# ai.net
KiCad netlist of a schematic drawn in Altium Designer
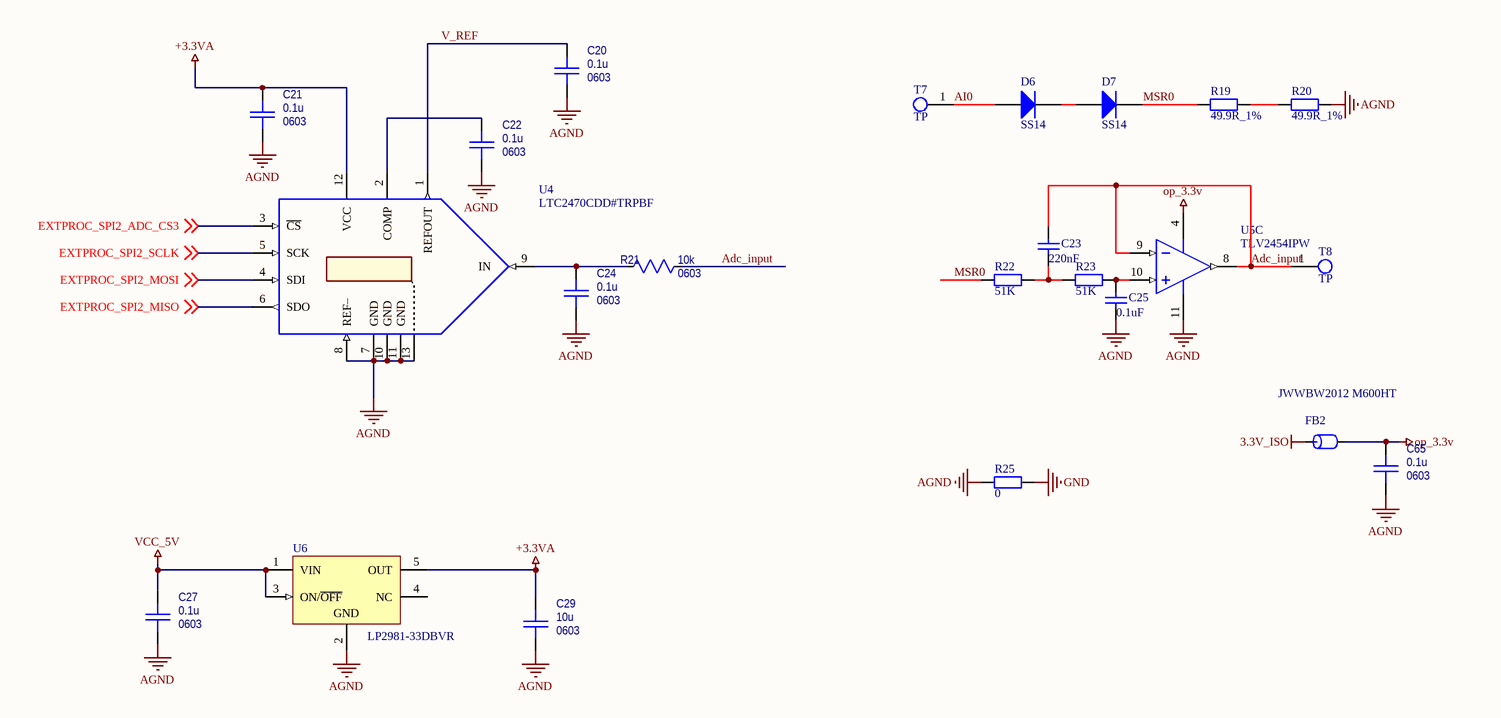
[diagram p0: ai.SchDoc]

(export (version "E")
  (design (tool "Eeschema 10.0.6"))
  (components
    (comp (ref "C20")
      (value "0.1u")
      (footprint "CAPC1608X092N_0603")
      (description "Capacitor, MLCC")
      (fields
        (field (name "PARTNUMBER") "C0603C104M5RACTU")
        (field (name "TOLERANCE") "[tol]")
        (field (name "PACKAGE") "0603")
      )
      (libsource (lib "Karl") (part "Capacitor_0603"))
    )
    (comp (ref "C21")
      (value "0.1u")
      (footprint "CAPC1608X092N_0603")
      (description "Capacitor, MLCC")
      (fields
        (field (name "PARTNUMBER") "C0603C104M5RACTU")
        (field (name "TOLERANCE") "[tol]")
        (field (name "PACKAGE") "0603")
      )
      (libsource (lib "Karl") (part "Capacitor_0603"))
    )
    (comp (ref "C22")
      (value "0.1u")
      (footprint "CAPC1608X092N_0603")
      (description "Capacitor, MLCC")
      (fields
        (field (name "PARTNUMBER") "C0603C104M5RACTU")
        (field (name "TOLERANCE") "[tol]")
        (field (name "PACKAGE") "0603")
      )
      (libsource (lib "Karl") (part "Capacitor_0603"))
    )
    (comp (ref "C23")
      (value "220nF")
      (footprint "0805C")
      (description "Capacitor")
      (fields (field (name "PUBLISHER") "Altium Limited"))
      (libsource (lib "Miscellaneous Devices") (part "Cap"))
    )
    (comp (ref "C24")
      (value "0.1u")
      (footprint "CAPC1608X092N_0603")
      (description "Capacitor, MLCC")
      (fields
        (field (name "PARTNUMBER") "C0603C104M5RACTU")
        (field (name "TOLERANCE") "[tol]")
        (field (name "PACKAGE") "0603")
      )
      (libsource (lib "Karl") (part "Capacitor_0603"))
    )
    (comp (ref "C25")
      (value "0.1uF")
      (footprint "0603C")
      (description "Capacitor")
      (fields (field (name "PUBLISHER") "Altium Limited"))
      (libsource (lib "Miscellaneous Devices") (part "Cap"))
    )
    (comp (ref "C27")
      (value "0.1u")
      (footprint "CAPC1608X092N_0603")
      (description "Capacitor, MLCC")
      (fields
        (field (name "PARTNUMBER") "C0603C104M5RACTU")
        (field (name "TOLERANCE") "[tol]")
        (field (name "PACKAGE") "0603")
      )
      (libsource (lib "Karl") (part "Capacitor_0603"))
    )
    (comp (ref "C29")
      (value "10u")
      (footprint "CAPC1608X092N_0603")
      (description "Capacitor, MLCC")
      (fields
        (field (name "PARTNUMBER") "GRM188R61A106KE69D")
        (field (name "TOLERANCE") "[tol]")
        (field (name "PACKAGE") "0603")
      )
      (libsource (lib "Karl") (part "Capacitor_0603"))
    )
    (comp (ref "C65")
      (value "0.1u")
      (footprint "CAPC1608X092N_0603")
      (description "Capacitor, MLCC")
      (fields
        (field (name "PARTNUMBER") "C0603C104M5RACTU")
        (field (name "TOLERANCE") "[tol]")
        (field (name "PACKAGE") "0603")
      )
      (libsource (lib "Karl") (part "Capacitor_0603"))
    )
    (comp (ref "D6")
      (value "SS14")
      (footprint "DO-214AC")
      (description "Default Diode")
      (fields (field (name "PUBLISHER") "Altium Limited"))
      (libsource (lib "Miscellaneous Devices") (part "Diode"))
    )
    (comp (ref "D7")
      (value "SS14")
      (footprint "DO-214AC")
      (description "Default Diode")
      (fields (field (name "PUBLISHER") "Altium Limited"))
      (libsource (lib "Miscellaneous Devices") (part "Diode"))
    )
    (comp (ref "FB2")
      (value "JWWBW2012 M600HT")
      (footprint "0805R")
      (libsource (lib "Schlib_20110825") (part "FB"))
    )
    (comp (ref "R19") (value "49.9R_1%") (footprint "0805R") (libsource (lib "MQlibrary") (part "Res0805M")))
    (comp (ref "R20") (value "49.9R_1%") (footprint "0805R") (libsource (lib "MQlibrary") (part "Res0805M")))
    (comp (ref "R21")
      (value "10k")
      (footprint "RESC1608X055N_0603")
      (description "Resistor, Standard")
      (fields
        (field (name "PARTNUMBER") "RR0816P-103-D")
        (field (name "TOLERANCE") "tol")
        (field (name "PACKAGE") "0603")
      )
      (libsource (lib "Karl") (part "Resistor_0603"))
    )
    (comp (ref "R22") (value "51K") (footprint "0603R") (libsource (lib "MQlibrary") (part "Res0805M")))
    (comp (ref "R23") (value "51K") (footprint "0603R") (libsource (lib "MQlibrary") (part "Res0805M")))
    (comp (ref "R25") (value "0") (footprint "1206R") (libsource (lib "MQlibrary") (part "Res0805M")))
    (comp (ref "T7") (value "TP") (footprint "TPD") (libsource (lib "Schlib_20110825") (part "TP")))
    (comp (ref "T8") (value "TP") (footprint "TPD") (libsource (lib "Schlib_20110825") (part "TP")))
    (comp (ref "U4")
      (value "LTC2470CDD#TRPBF")
      (footprint "LT-DD-12_V")
      (description "16-bit Analog-to-digital Converters, 12-pin SON (DD-12), 0 to 70 degC, Pb-Free, Tape and Reel")
      (libsource (lib "Bogen") (part "LTC2470CDD#TRPBF"))
    )
    (comp (ref "U5")
      (value "TLV2454IPW")
      (footprint "TSSOP14")
      (description "Quad High-speed, Ultra Low-power, Single-Supply TTL comparator")
      (fields (field (name "PUBLISHER") "Altium Limited"))
      (libsource (lib "Maxim Analog Comparator") (part "MAX908EPD"))
    )
    (comp (ref "U6")
      (value "LP2981-33DBVR")
      (footprint "DBV0005A_M")
      (description "Micropower 100 mA Ultra Low-Dropout Regulator, 5-pin SOT-23, Pb-Free")
      (libsource (lib "Bogen") (part "LP2981-33DBVR"))
    )
  )
  (nets
    (net (code "1") (name "+3.3VA") (class "Default")
      (node (ref "C21") (pin "1") (pinfunction "1_1") (pintype "passive"))
      (node (ref "C29") (pin "1") (pinfunction "1_1") (pintype "passive"))
      (node (ref "U4") (pin "12") (pinfunction "VCC_12") (pintype "power_in"))
      (node (ref "U6") (pin "5") (pinfunction "OUT_5") (pintype "power_in"))
    )
    (net (code "2") (name "/AI0") (class "Default")
      (node (ref "D6") (pin "1") (pinfunction "A_1") (pintype "passive"))
      (node (ref "T7") (pin "1") (pintype "passive"))
    )
    (net (code "3") (name "/Adc_input") (class "Default")
      (node (ref "C23") (pin "2") (pinfunction "2_2") (pintype "passive"))
      (node (ref "R21") (pin "1") (pinfunction "1_1") (pintype "passive"))
      (node (ref "T8") (pin "1") (pintype "passive"))
      (node (ref "U5") (pin "8") (pinfunction "OUT_8") (pintype "output"))
      (node (ref "U5") (pin "9") (pinfunction "IN-_9") (pintype "input"))
    )
    (net (code "4") (name "/MSR0") (class "Default")
      (node (ref "D7") (pin "2") (pinfunction "K_2") (pintype "passive"))
      (node (ref "R19") (pin "2") (pinfunction "2_2") (pintype "passive"))
      (node (ref "R22") (pin "2") (pinfunction "2_2") (pintype "passive"))
    )
    (net (code "5") (name "/V_REF") (class "Default")
      (node (ref "C20") (pin "1") (pinfunction "1_1") (pintype "passive"))
      (node (ref "U4") (pin "1") (pinfunction "REFOUT_1") (pintype "output"))
    )
    (net (code "6") (name "3.3V_ISO") (class "Default") (node (ref "FB2") (pin "1") (pintype "passive")))
    (net (code "7") (name "AGND") (class "Default")
      (node (ref "C20") (pin "2") (pinfunction "2_2") (pintype "passive"))
      (node (ref "C21") (pin "2") (pinfunction "2_2") (pintype "passive"))
      (node (ref "C22") (pin "2") (pinfunction "2_2") (pintype "passive"))
      (node (ref "C24") (pin "2") (pinfunction "2_2") (pintype "passive"))
      (node (ref "C25") (pin "1") (pinfunction "1_1") (pintype "passive"))
      (node (ref "C27") (pin "2") (pinfunction "2_2") (pintype "passive"))
      (node (ref "C29") (pin "2") (pinfunction "2_2") (pintype "passive"))
      (node (ref "C65") (pin "2") (pinfunction "2_2") (pintype "passive"))
      (node (ref "R20") (pin "1") (pinfunction "1_1") (pintype "passive"))
      (node (ref "R25") (pin "2") (pinfunction "2_2") (pintype "passive"))
      (node (ref "U4") (pin "10") (pinfunction "GND_10") (pintype "power_in"))
      (node (ref "U4") (pin "11") (pinfunction "GND_11") (pintype "power_in"))
      (node (ref "U4") (pin "13") (pinfunction "EP_13") (pintype "power_in"))
      (node (ref "U4") (pin "7") (pinfunction "GND_7") (pintype "power_in"))
      (node (ref "U4") (pin "8") (pinfunction "REF–_8") (pintype "input"))
      (node (ref "U5") (pin "11") (pinfunction "GND_11") (pintype "power_in"))
      (node (ref "U6") (pin "2") (pinfunction "GND_2") (pintype "power_in"))
    )
    (net (code "8") (name "EXTPROC_SPI2_ADC_CS3") (class "Default")
      (node (ref "U4") (pin "3") (pinfunction "~{CS}_3") (pintype "input"))
    )
    (net (code "9") (name "EXTPROC_SPI2_MISO") (class "Default")
      (node (ref "U4") (pin "6") (pinfunction "SDO_6") (pintype "output"))
    )
    (net (code "10") (name "EXTPROC_SPI2_MOSI") (class "Default")
      (node (ref "U4") (pin "4") (pinfunction "SDI_4") (pintype "input"))
    )
    (net (code "11") (name "EXTPROC_SPI2_SCLK") (class "Default")
      (node (ref "U4") (pin "5") (pinfunction "SCK_5") (pintype "input"))
    )
    (net (code "12") (name "GND") (class "Default")
      (node (ref "R25") (pin "1") (pinfunction "1_1") (pintype "passive"))
    )
    (net (code "13") (name "Net-(C23-Pad1)") (class "Default")
      (node (ref "C23") (pin "1") (pinfunction "1_1") (pintype "passive"))
      (node (ref "R22") (pin "1") (pinfunction "1_1") (pintype "passive"))
      (node (ref "R23") (pin "2") (pinfunction "2_2") (pintype "passive"))
    )
    (net (code "14") (name "Net-(D6-K)") (class "Default")
      (node (ref "D6") (pin "2") (pinfunction "K_2") (pintype "passive"))
      (node (ref "D7") (pin "1") (pinfunction "A_1") (pintype "passive"))
    )
    (net (code "15") (name "Net-(R19-Pad1)") (class "Default")
      (node (ref "R19") (pin "1") (pinfunction "1_1") (pintype "passive"))
      (node (ref "R20") (pin "2") (pinfunction "2_2") (pintype "passive"))
    )
    (net (code "16") (name "Net-(U4-COMP)") (class "Default")
      (node (ref "C22") (pin "1") (pinfunction "1_1") (pintype "passive"))
      (node (ref "U4") (pin "2") (pinfunction "COMP_2") (pintype "passive"))
    )
    (net (code "17") (name "Net-(U4-IN)") (class "Default")
      (node (ref "C24") (pin "1") (pinfunction "1_1") (pintype "passive"))
      (node (ref "R21") (pin "2") (pinfunction "2_2") (pintype "passive"))
      (node (ref "U4") (pin "9") (pinfunction "IN_9") (pintype "input"))
    )
    (net (code "18") (name "Net-(U5C-IN+)") (class "Default")
      (node (ref "C25") (pin "2") (pinfunction "2_2") (pintype "passive"))
      (node (ref "R23") (pin "1") (pinfunction "1_1") (pintype "passive"))
      (node (ref "U5") (pin "10") (pinfunction "IN+_10") (pintype "input"))
    )
    (net (code "19") (name "VCC_5V") (class "Default")
      (node (ref "C27") (pin "1") (pinfunction "1_1") (pintype "passive"))
      (node (ref "U6") (pin "1") (pinfunction "VIN_1") (pintype "power_in"))
      (node (ref "U6") (pin "3") (pinfunction "ON/~{OFF}_3") (pintype "input"))
    )
    (net (code "20") (name "op_3.3v") (class "Default")
      (node (ref "C65") (pin "1") (pinfunction "1_1") (pintype "passive"))
      (node (ref "FB2") (pin "2") (pintype "passive"))
      (node (ref "U5") (pin "4") (pinfunction "V+_4") (pintype "power_in"))
    )
    (net (code "21") (name "unconnected-(U6-NC-Pad4)") (class "Default")
      (node (ref "U6") (pin "4") (pinfunction "NC_4") (pintype "passive"))
    )
  )
)
